# Power.net
KiCad netlist of a schematic drawn in Altium Designer
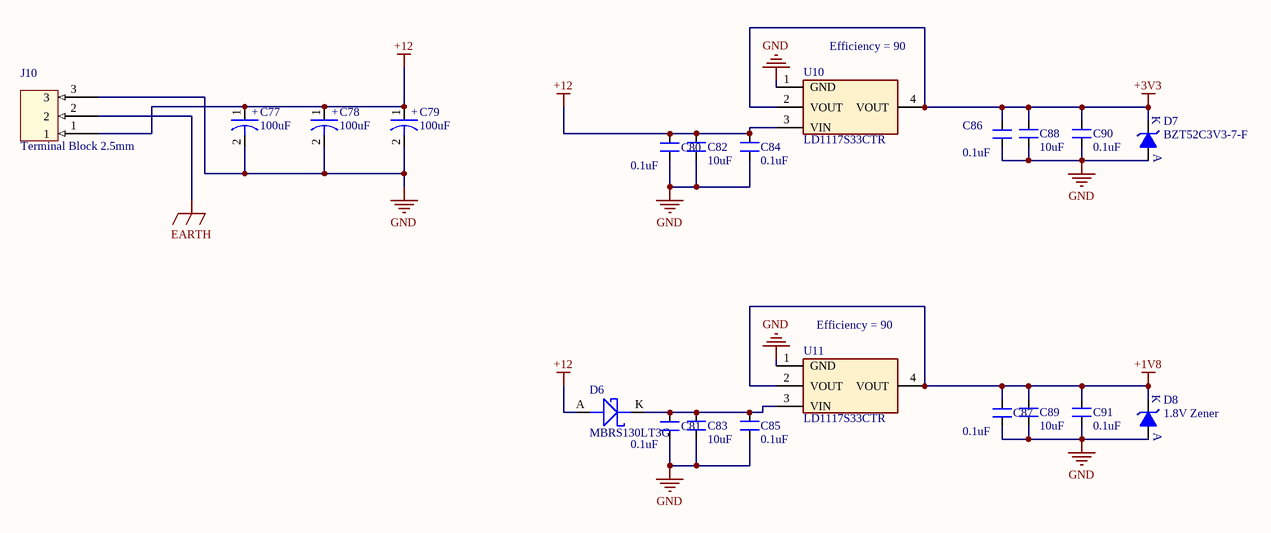
[diagram p0: Power.SchDoc]

(export (version "E")
  (design (tool "Eeschema 10.0.6"))
  (components
    (comp (ref "C77")
      (value "100uF")
      (footprint "ACAP_P305_D393_H393_RAD")
      (description "100µF 50V Aluminum Polymer Capacitor Radial, Can - SMD 28mOhm 4000 Hrs @ 125°C")
      (fields
        (field (name "MANUFACTURER") "Nichicon")
        (field (name "MANUFACTURER PART NUMBER") "GYA1H101MCQ1GS")
      )
      (libsource (lib "ESTEEMPCBLIB") (part "CAP-P_100uF-50V-20%-RAD"))
    )
    (comp (ref "C78")
      (value "100uF")
      (footprint "ACAP_P305_D393_H393_RAD")
      (description "100µF 50V Aluminum Polymer Capacitor Radial, Can - SMD 28mOhm 4000 Hrs @ 125°C")
      (fields
        (field (name "MANUFACTURER") "Nichicon")
        (field (name "MANUFACTURER PART NUMBER") "GYA1H101MCQ1GS")
      )
      (libsource (lib "ESTEEMPCBLIB") (part "CAP-P_100uF-50V-20%-RAD"))
    )
    (comp (ref "C79")
      (value "100uF")
      (footprint "ACAP_P305_D393_H393_RAD")
      (description "100µF 50V Aluminum Polymer Capacitor Radial, Can - SMD 28mOhm 4000 Hrs @ 125°C")
      (fields
        (field (name "MANUFACTURER") "Nichicon")
        (field (name "MANUFACTURER PART NUMBER") "GYA1H101MCQ1GS")
      )
      (libsource (lib "ESTEEMPCBLIB") (part "CAP-P_100uF-50V-20%-RAD"))
    )
    (comp (ref "C80")
      (value "0.1uF")
      (footprint "CAP_0805")
      (description "0.1µF ±20% 50V Ceramic Capacitor X7R 0805 (2012 Metric)")
      (fields
        (field (name "MANUFACTURER") "Samsung Electro-Mechanics")
        (field (name "MANUFACTURER PART NUMBER") "CL21B104MBCNNNC")
      )
      (libsource (lib "ESTEEMPCBLIB") (part "CAP_0.1uF-50V-20%-0805"))
    )
    (comp (ref "C81")
      (value "0.1uF")
      (footprint "CAP_0805")
      (description "0.1µF ±20% 50V Ceramic Capacitor X7R 0805 (2012 Metric)")
      (fields
        (field (name "MANUFACTURER") "Samsung Electro-Mechanics")
        (field (name "MANUFACTURER PART NUMBER") "CL21B104MBCNNNC")
      )
      (libsource (lib "ESTEEMPCBLIB") (part "CAP_0.1uF-50V-20%-0805"))
    )
    (comp (ref "C82")
      (value "10uF")
      (footprint "CAP_1206")
      (description "10µF ±10% 50V Ceramic Capacitor X7R 1206 (3216 Metric)")
      (fields
        (field (name "MANUFACTURER") "KEMET")
        (field (name "MANUFACTURER PART NUMBER") "CL31B106KBHNNNE")
      )
      (libsource (lib "ESTEEMPCBLIB") (part "CAP_10uF-50V-10%-1206"))
    )
    (comp (ref "C83")
      (value "10uF")
      (footprint "CAP_1206")
      (description "10µF ±10% 50V Ceramic Capacitor X7R 1206 (3216 Metric)")
      (fields
        (field (name "MANUFACTURER") "KEMET")
        (field (name "MANUFACTURER PART NUMBER") "CL31B106KBHNNNE")
      )
      (libsource (lib "ESTEEMPCBLIB") (part "CAP_10uF-50V-10%-1206"))
    )
    (comp (ref "C84")
      (value "0.1uF")
      (footprint "CAP_0805")
      (description "0.1µF ±10% 50V Ceramic Capacitor X7R 0805 (2012 Metric)")
      (fields
        (field (name "MANUFACTURER") "Samsung")
        (field (name "MANUFACTURER PART NUMBER") "CL21B104KBCNNNC")
      )
      (libsource (lib "ESTEEMPCBLIB") (part "CAP_0.1uF-50V-10%-0805"))
    )
    (comp (ref "C85")
      (value "0.1uF")
      (footprint "CAP_0805")
      (description "0.1µF ±10% 50V Ceramic Capacitor X7R 0805 (2012 Metric)")
      (fields
        (field (name "MANUFACTURER") "Samsung")
        (field (name "MANUFACTURER PART NUMBER") "CL21B104KBCNNNC")
      )
      (libsource (lib "ESTEEMPCBLIB") (part "CAP_0.1uF-50V-10%-0805"))
    )
    (comp (ref "C86")
      (value "0.1uF")
      (footprint "CAP_0805")
      (description "0.1µF ±20% 50V Ceramic Capacitor X7R 0805 (2012 Metric)")
      (fields
        (field (name "MANUFACTURER") "Samsung Electro-Mechanics")
        (field (name "MANUFACTURER PART NUMBER") "CL21B104MBCNNNC")
      )
      (libsource (lib "ESTEEMPCBLIB") (part "CAP_0.1uF-50V-20%-0805"))
    )
    (comp (ref "C87")
      (value "0.1uF")
      (footprint "CAP_0805")
      (description "0.1µF ±20% 50V Ceramic Capacitor X7R 0805 (2012 Metric)")
      (fields
        (field (name "MANUFACTURER") "Samsung Electro-Mechanics")
        (field (name "MANUFACTURER PART NUMBER") "CL21B104MBCNNNC")
      )
      (libsource (lib "ESTEEMPCBLIB") (part "CAP_0.1uF-50V-20%-0805"))
    )
    (comp (ref "C88")
      (value "10uF")
      (footprint "CAP_1206")
      (description "10µF ±10% 50V Ceramic Capacitor X7R 1206 (3216 Metric)")
      (fields
        (field (name "MANUFACTURER") "KEMET")
        (field (name "MANUFACTURER PART NUMBER") "CL31B106KBHNNNE")
      )
      (libsource (lib "ESTEEMPCBLIB") (part "CAP_10uF-50V-10%-1206"))
    )
    (comp (ref "C89")
      (value "10uF")
      (footprint "CAP_1206")
      (description "10µF ±10% 50V Ceramic Capacitor X7R 1206 (3216 Metric)")
      (fields
        (field (name "MANUFACTURER") "KEMET")
        (field (name "MANUFACTURER PART NUMBER") "CL31B106KBHNNNE")
      )
      (libsource (lib "ESTEEMPCBLIB") (part "CAP_10uF-50V-10%-1206"))
    )
    (comp (ref "C90")
      (value "0.1uF")
      (footprint "CAP_0805")
      (description "0.1µF ±10% 50V Ceramic Capacitor X7R 0805 (2012 Metric)")
      (fields
        (field (name "MANUFACTURER") "Samsung")
        (field (name "MANUFACTURER PART NUMBER") "CL21B104KBCNNNC")
      )
      (libsource (lib "ESTEEMPCBLIB") (part "CAP_0.1uF-50V-10%-0805"))
    )
    (comp (ref "C91")
      (value "0.1uF")
      (footprint "CAP_0805")
      (description "0.1µF ±10% 50V Ceramic Capacitor X7R 0805 (2012 Metric)")
      (fields
        (field (name "MANUFACTURER") "Samsung")
        (field (name "MANUFACTURER PART NUMBER") "CL21B104KBCNNNC")
      )
      (libsource (lib "ESTEEMPCBLIB") (part "CAP_0.1uF-50V-10%-0805"))
    )
    (comp (ref "D6")
      (value "MBRS130LT3G")
      (footprint "DIO_SMB_DO-214AA")
      (description "Diode Schottky 30V 2A Surface Mount SMB")
      (fields (field (name "MANUFACTURER") "ON Semiconductor"))
      (libsource (lib "ESTEEMPCBLIB") (part "DIO-S_445mV-30V-2A-SMB"))
    )
    (comp (ref "D7")
      (value "BZT52C3V3-7-F")
      (footprint "DIO_SOD-123")
      (description "Zener Diode 3.3V 500mW ±6% Surface Mount SOD-123")
      (fields (field (name "MANUFACTURER") "Diodes Incorporated"))
      (libsource (lib "ESTEEMPCBLIB") (part "DIO-Z_3.3V-500mW-SOD123"))
    )
    (comp (ref "D8")
      (value "1.8V Zener")
      (footprint "DIO_DO-213AB_SMD")
      (description "Zener Diode 1.8V 500mW ±5% Surface Mount DO-213AA")
      (libsource (lib "ESTEEMPCBLIB") (part "DIO-Z_1.8V-500mW-DO213AA"))
    )
    (comp (ref "J10")
      (value "Terminal Block 2.5mm")
      (footprint "CON3_100_TB_TH_ST")
      (description "3 Pins, 1 Row 2.54mm Pitch, straight Connector, male")
      (fields
        (field (name "MANUFACTURER PART NUMBER") "1725669")
        (field (name "MANUFACTURER") "Phoenix Contact")
      )
      (libsource (lib "ESTEEMPCBLIB") (part "CON-TB_3X1-100-ST-TH"))
    )
    (comp (ref "U10")
      (value "LD1117S33CTR")
      (footprint "SOT223_3")
      (description "Linear Voltage Regulator IC 1 Output 800mA SOT-223")
      (fields (field (name "MANUFACTURER") "STMicroelectronics"))
      (libsource (lib "ESTEEMPCBLIB") (part "REG_15V-3.3V-0.9A-12W-SOT223"))
    )
    (comp (ref "U11")
      (value "LD1117S33CTR")
      (footprint "SOT223_3")
      (description "Linear Voltage Regulator IC 1 Output 800mA SOT-223")
      (fields (field (name "MANUFACTURER") "STMicroelectronics"))
      (libsource (lib "ESTEEMPCBLIB") (part "REG_15V-3.3V-0.9A-12W-SOT223"))
    )
  )
  (nets
    (net (code "1") (name "+1V8") (class "Default")
      (node (ref "C87") (pin "2") (pinfunction "2_2") (pintype "passive"))
      (node (ref "C89") (pin "2") (pinfunction "2_2") (pintype "passive"))
      (node (ref "C91") (pin "2") (pinfunction "2_2") (pintype "passive"))
      (node (ref "D8") (pin "K") (pinfunction "K_K") (pintype "passive"))
      (node (ref "U11") (pin "2") (pinfunction "VOUT_2") (pintype "passive"))
      (node (ref "U11") (pin "4") (pinfunction "VOUT_4") (pintype "passive"))
    )
    (net (code "2") (name "+3V3") (class "Default")
      (node (ref "C86") (pin "2") (pinfunction "2_2") (pintype "passive"))
      (node (ref "C88") (pin "2") (pinfunction "2_2") (pintype "passive"))
      (node (ref "C90") (pin "2") (pinfunction "2_2") (pintype "passive"))
      (node (ref "D7") (pin "K") (pinfunction "K_K") (pintype "passive"))
      (node (ref "U10") (pin "2") (pinfunction "VOUT_2") (pintype "passive"))
      (node (ref "U10") (pin "4") (pinfunction "VOUT_4") (pintype "passive"))
    )
    (net (code "3") (name "+12") (class "Default")
      (node (ref "C77") (pin "1") (pinfunction "1_1") (pintype "passive"))
      (node (ref "C78") (pin "1") (pinfunction "1_1") (pintype "passive"))
      (node (ref "C79") (pin "1") (pinfunction "1_1") (pintype "passive"))
      (node (ref "C80") (pin "2") (pinfunction "2_2") (pintype "passive"))
      (node (ref "C82") (pin "2") (pinfunction "2_2") (pintype "passive"))
      (node (ref "C84") (pin "2") (pinfunction "2_2") (pintype "passive"))
      (node (ref "D6") (pin "A") (pinfunction "A_A") (pintype "passive"))
      (node (ref "J10") (pin "1") (pinfunction "1_1") (pintype "input"))
      (node (ref "U10") (pin "3") (pinfunction "VIN_3") (pintype "passive"))
    )
    (net (code "4") (name "EARTH") (class "Default")
      (node (ref "J10") (pin "2") (pinfunction "2_2") (pintype "input"))
    )
    (net (code "5") (name "GND") (class "Default")
      (node (ref "C77") (pin "2") (pinfunction "2_2") (pintype "passive"))
      (node (ref "C78") (pin "2") (pinfunction "2_2") (pintype "passive"))
      (node (ref "C79") (pin "2") (pinfunction "2_2") (pintype "passive"))
      (node (ref "C80") (pin "1") (pinfunction "1_1") (pintype "passive"))
      (node (ref "C81") (pin "1") (pinfunction "1_1") (pintype "passive"))
      (node (ref "C82") (pin "1") (pinfunction "1_1") (pintype "passive"))
      (node (ref "C83") (pin "1") (pinfunction "1_1") (pintype "passive"))
      (node (ref "C84") (pin "1") (pinfunction "1_1") (pintype "passive"))
      (node (ref "C85") (pin "1") (pinfunction "1_1") (pintype "passive"))
      (node (ref "C86") (pin "1") (pinfunction "1_1") (pintype "passive"))
      (node (ref "C87") (pin "1") (pinfunction "1_1") (pintype "passive"))
      (node (ref "C88") (pin "1") (pinfunction "1_1") (pintype "passive"))
      (node (ref "C89") (pin "1") (pinfunction "1_1") (pintype "passive"))
      (node (ref "C90") (pin "1") (pinfunction "1_1") (pintype "passive"))
      (node (ref "C91") (pin "1") (pinfunction "1_1") (pintype "passive"))
      (node (ref "D7") (pin "A") (pinfunction "A_A") (pintype "passive"))
      (node (ref "D8") (pin "A") (pinfunction "A_A") (pintype "passive"))
      (node (ref "J10") (pin "3") (pinfunction "3_3") (pintype "input"))
      (node (ref "U10") (pin "1") (pinfunction "GND_1") (pintype "passive"))
      (node (ref "U11") (pin "1") (pinfunction "GND_1") (pintype "passive"))
    )
    (net (code "6") (name "Net-(U11-VIN)") (class "Default")
      (node (ref "C81") (pin "2") (pinfunction "2_2") (pintype "passive"))
      (node (ref "C83") (pin "2") (pinfunction "2_2") (pintype "passive"))
      (node (ref "C85") (pin "2") (pinfunction "2_2") (pintype "passive"))
      (node (ref "D6") (pin "K") (pinfunction "K_K") (pintype "passive"))
      (node (ref "U11") (pin "3") (pinfunction "VIN_3") (pintype "passive"))
    )
  )
)
